# Sheet1.net
KiCad netlist of a schematic drawn in Altium Designer
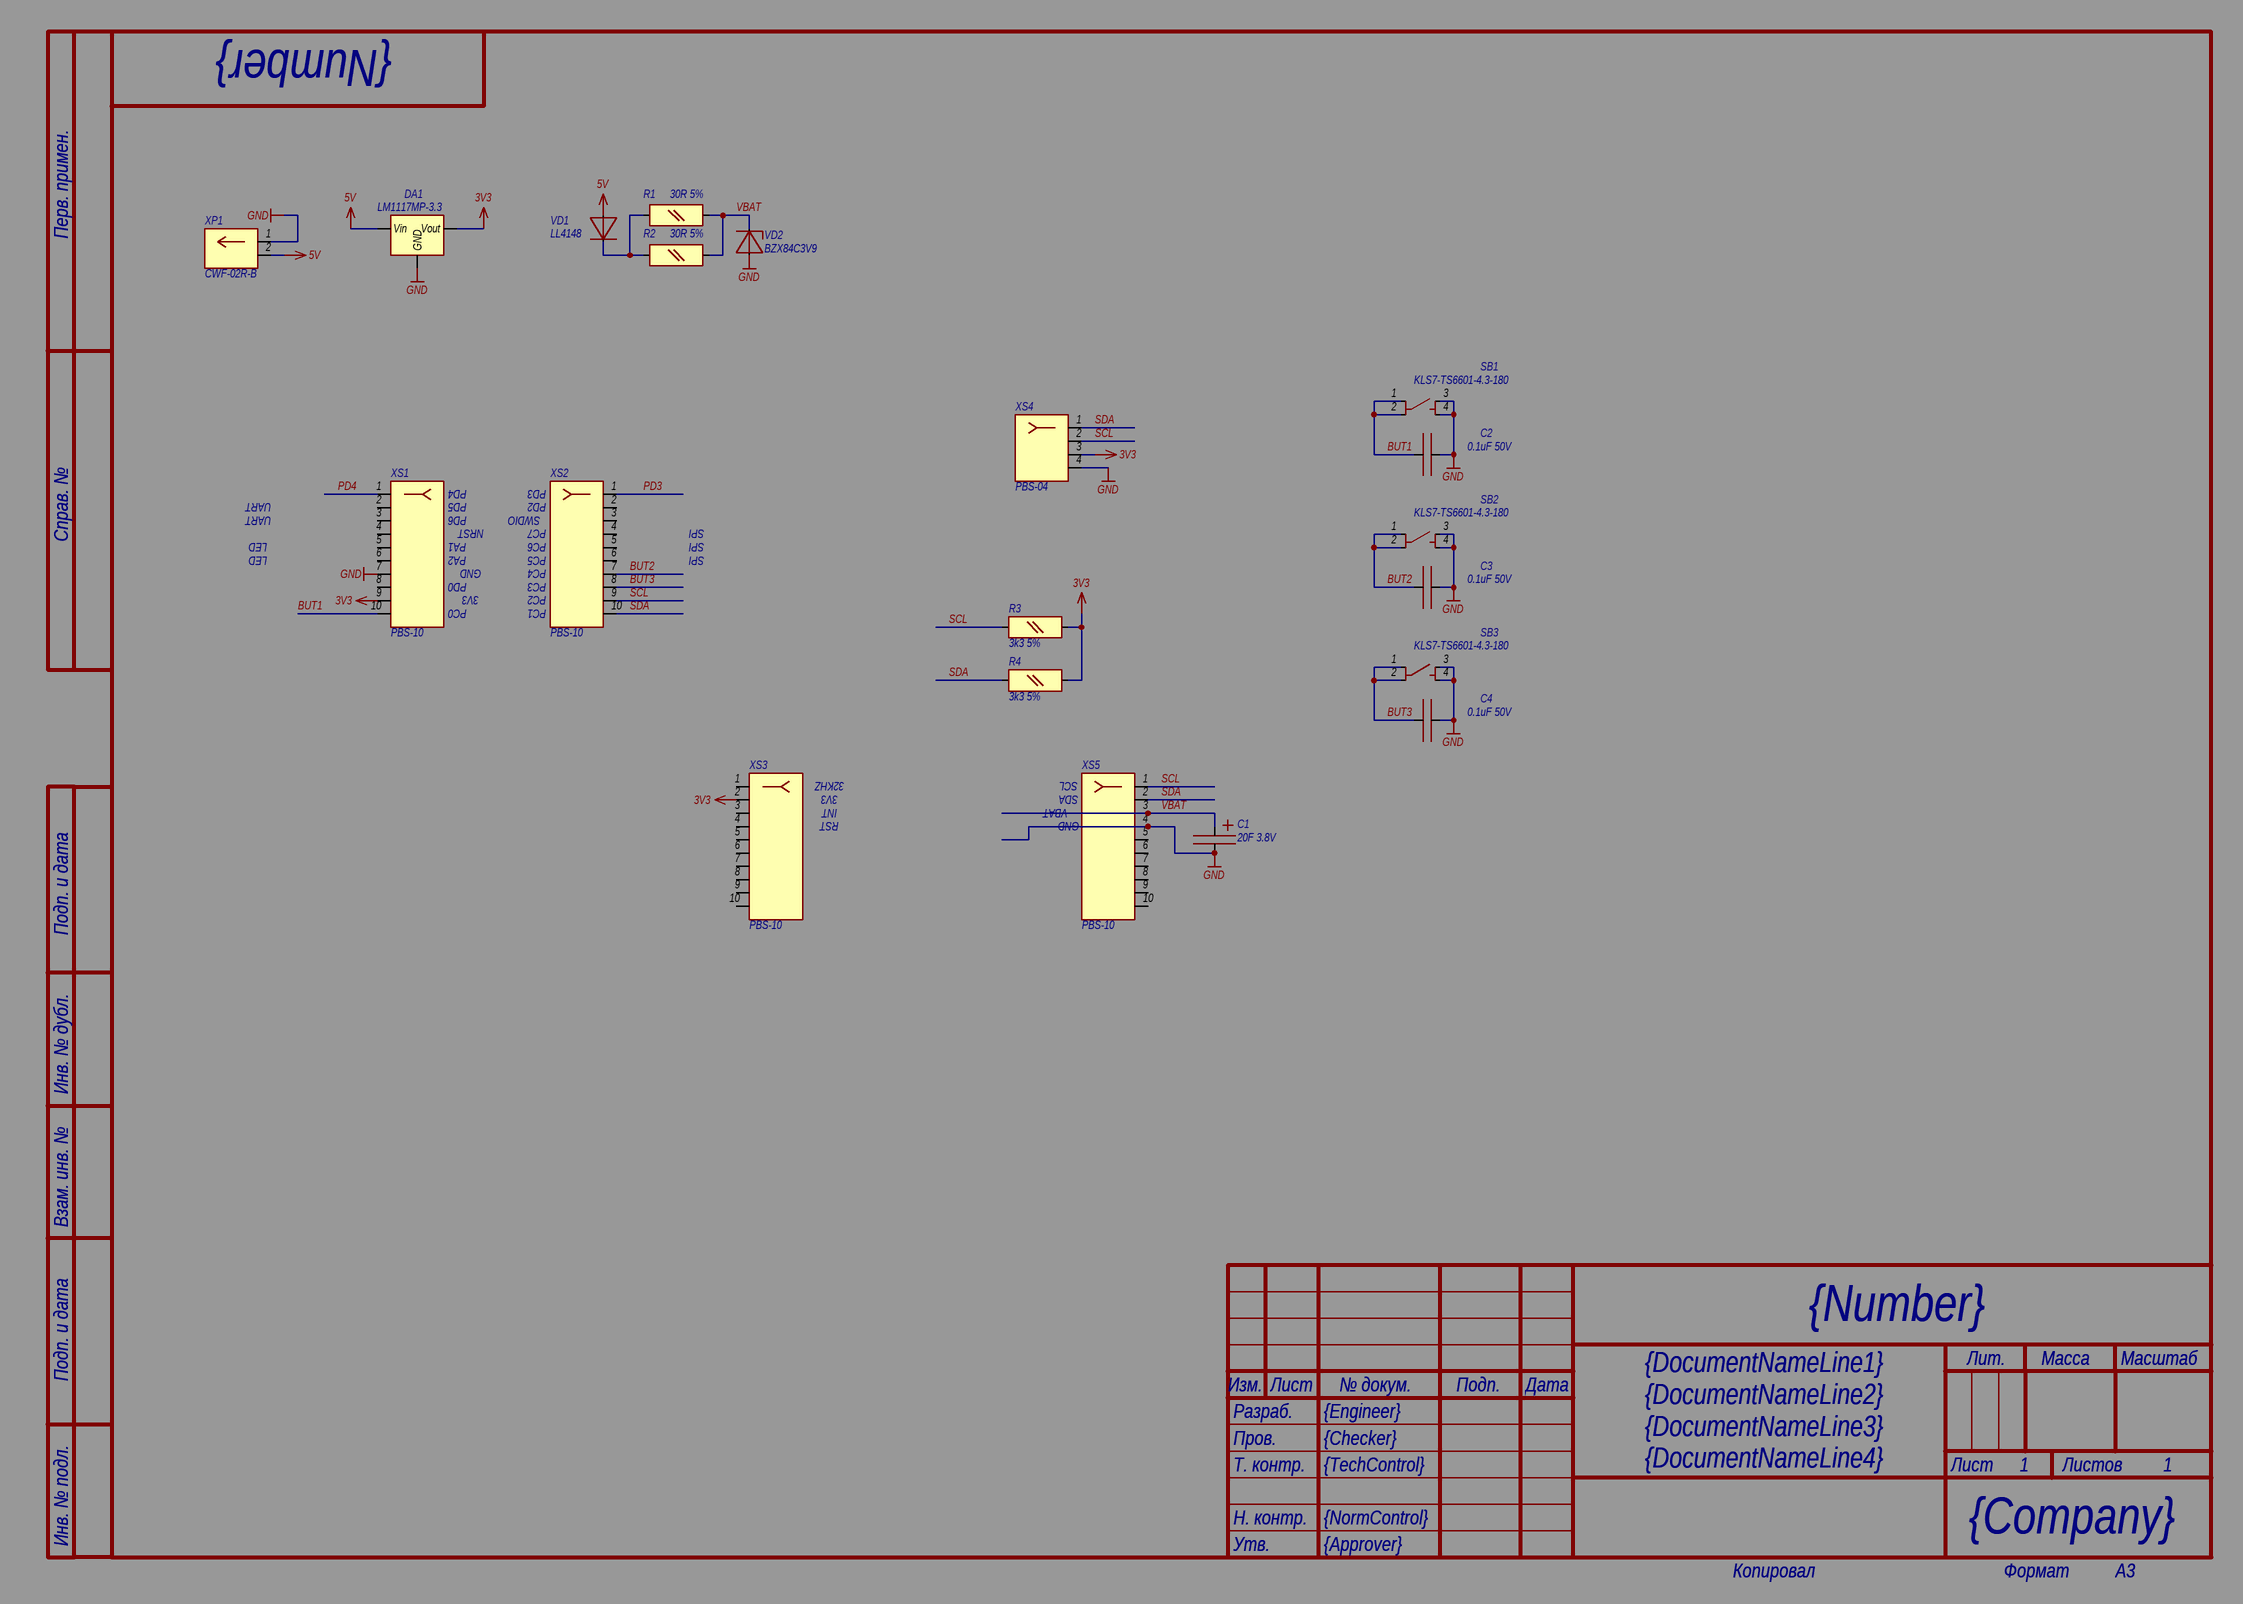
[diagram p0: Sheet1.SchDoc]

(export (version "E")
  (design (tool "Eeschema 10.0.6"))
  (components
    (comp (ref "C1")
      (value "20F 3.8V")
      (footprint "LIC0813")
      (description "Ионистор 20F 3.8V 0813")
      (fields (field (name "PART NUMBER") "LIC 0813 206"))
      (libsource (lib "ATwiceDB") (part "Cap_plus"))
    )
    (comp (ref "C2")
      (value "0.1uF 50V")
      (footprint "CAP SMD0805")
      (description "Конденсатор керамический SMD 0805 0.1uF 50V ±20%")
      (fields (field (name "PART NUMBER") "Cap 0805 0.1uF 50V"))
      (libsource (lib "ATwiceDB") (part "Cap"))
    )
    (comp (ref "C3")
      (value "0.1uF 50V")
      (footprint "CAP SMD0805")
      (description "Конденсатор керамический SMD 0805 0.1uF 50V ±20%")
      (fields (field (name "PART NUMBER") "Cap 0805 0.1uF 50V"))
      (libsource (lib "ATwiceDB") (part "Cap"))
    )
    (comp (ref "C4")
      (value "0.1uF 50V")
      (footprint "CAP SMD0805")
      (description "Конденсатор керамический SMD 0805 0.1uF 50V ±20%")
      (fields (field (name "PART NUMBER") "Cap 0805 0.1uF 50V"))
      (libsource (lib "ATwiceDB") (part "Cap"))
    )
    (comp (ref "DA1")
      (value "LM1117MP-3.3")
      (footprint "SOT223")
      (description "LDO стабилизатор")
      (libsource (lib "ATwiceDB") (part "LM1117"))
    )
    (comp (ref "R1")
      (value "30R 5%")
      (footprint "SMD 0805")
      (description "Резистор SMD 0805 30R 5%")
      (fields (field (name "PART NUMBER") "Res 0805 30R 5%"))
      (libsource (lib "ATwiceDB") (part "Res_0125"))
    )
    (comp (ref "R2")
      (value "30R 5%")
      (footprint "SMD 0805")
      (description "Резистор SMD 0805 30R 5%")
      (fields (field (name "PART NUMBER") "Res 0805 30R 5%"))
      (libsource (lib "ATwiceDB") (part "Res_0125"))
    )
    (comp (ref "R3")
      (value "3k3 5%")
      (footprint "SMD 0805")
      (description "Резистор SMD 0805 3k3 5%")
      (fields (field (name "PART NUMBER") "Res 0805 3k3 5%"))
      (libsource (lib "ATwiceDB") (part "Res_0125"))
    )
    (comp (ref "R4")
      (value "3k3 5%")
      (footprint "SMD 0805")
      (description "Резистор SMD 0805 3k3 5%")
      (fields (field (name "PART NUMBER") "Res 0805 3k3 5%"))
      (libsource (lib "ATwiceDB") (part "Res_0125"))
    )
    (comp (ref "SB1")
      (value "KLS7-TS6601-4.3-180")
      (footprint "KLS7-TS6601-4.3-180")
      (description "Кнопка тактовая KLS7-TS6601 6х6х4,3мм")
      (libsource (lib "ATwiceDB") (part "SB_TACT"))
    )
    (comp (ref "SB2")
      (value "KLS7-TS6601-4.3-180")
      (footprint "KLS7-TS6601-4.3-180")
      (description "Кнопка тактовая KLS7-TS6601 6х6х4,3мм")
      (libsource (lib "ATwiceDB") (part "SB_TACT"))
    )
    (comp (ref "SB3")
      (value "KLS7-TS6601-4.3-180")
      (footprint "KLS7-TS6601-4.3-180")
      (description "Кнопка тактовая KLS7-TS6601 6х6х4,3мм")
      (libsource (lib "ATwiceDB") (part "SB_TACT"))
    )
    (comp (ref "VD1")
      (value "LL4148")
      (footprint "MINIMELF")
      (description "Диод LL4148")
      (libsource (lib "ATwiceDB") (part "Diode"))
    )
    (comp (ref "VD2")
      (value "BZX84C3V9")
      (footprint "SOT23_1A3C")
      (description "Стабилитрон BZX84C3V9 SOT23")
      (libsource (lib "ATwiceDB") (part "Stab"))
    )
    (comp (ref "XP1")
      (value "CWF-02R-B")
      (footprint "CWF-02R-B")
      (description "Разъём CWF-02R-B вилка угловая 2,50мм тип B")
      (libsource (lib "ATwiceDB") (part "Conn_XP02"))
    )
    (comp (ref "XS1")
      (value "PBS-10")
      (footprint "PBS-10")
      (description "Разъём PBS-10 гнездо однорядное 2,54мм")
      (libsource (lib "") (part "Conn_XS10_1"))
    )
    (comp (ref "XS2")
      (value "PBS-10")
      (footprint "PBS-10")
      (description "Разъём PBS-10 гнездо однорядное 2,54мм")
      (libsource (lib "ATwiceDB") (part "Conn_XS10"))
    )
    (comp (ref "XS3")
      (value "PBS-10")
      (footprint "PBS-10")
      (description "Разъём PBS-10 гнездо однорядное 2,54мм")
      (libsource (lib "") (part "Conn_XS10_1"))
    )
    (comp (ref "XS4")
      (value "PBS-04")
      (footprint "PBS-04")
      (description "Разъём PBS-04 гнездо однорядное 2,54мм")
      (libsource (lib "ATwiceDB") (part "Conn_XS04"))
    )
    (comp (ref "XS5")
      (value "PBS-10")
      (footprint "PBS-10")
      (description "Разъём PBS-10 гнездо однорядное 2,54мм")
      (libsource (lib "ATwiceDB") (part "Conn_XS10"))
    )
  )
  (nets
    (net (code "1") (name "/BUT1") (class "Default")
      (node (ref "C2") (pin "1") (pinfunction "1_1") (pintype "passive"))
      (node (ref "SB1") (pin "1") (pinfunction "1_1") (pintype "passive"))
      (node (ref "SB1") (pin "2") (pinfunction "2_2") (pintype "passive"))
      (node (ref "XS1") (pin "10") (pintype "passive"))
    )
    (net (code "2") (name "/BUT2") (class "Default")
      (node (ref "C3") (pin "1") (pinfunction "1_1") (pintype "passive"))
      (node (ref "SB2") (pin "1") (pinfunction "1_1") (pintype "passive"))
      (node (ref "SB2") (pin "2") (pinfunction "2_2") (pintype "passive"))
      (node (ref "XS2") (pin "7") (pintype "passive"))
    )
    (net (code "3") (name "/BUT3") (class "Default")
      (node (ref "C4") (pin "1") (pinfunction "1_1") (pintype "passive"))
      (node (ref "SB3") (pin "1") (pinfunction "1_1") (pintype "passive"))
      (node (ref "SB3") (pin "2") (pinfunction "2_2") (pintype "passive"))
      (node (ref "XS2") (pin "8") (pintype "passive"))
    )
    (net (code "4") (name "/PD3") (class "Default") (node (ref "XS2") (pin "1") (pintype "passive")))
    (net (code "5") (name "/PD4") (class "Default") (node (ref "XS1") (pin "1") (pintype "passive")))
    (net (code "6") (name "/SCL") (class "Default")
      (node (ref "R3") (pin "1") (pinfunction "1_1") (pintype "passive"))
      (node (ref "XS2") (pin "9") (pintype "passive"))
      (node (ref "XS4") (pin "2") (pintype "passive"))
      (node (ref "XS5") (pin "1") (pintype "passive"))
    )
    (net (code "7") (name "/SDA") (class "Default")
      (node (ref "R4") (pin "1") (pinfunction "1_1") (pintype "passive"))
      (node (ref "XS2") (pin "10") (pintype "passive"))
      (node (ref "XS4") (pin "1") (pintype "passive"))
      (node (ref "XS5") (pin "2") (pintype "passive"))
    )
    (net (code "8") (name "/VBAT") (class "Default")
      (node (ref "C1") (pin "1") (pinfunction "1_1") (pintype "passive"))
      (node (ref "R1") (pin "2") (pinfunction "2_2") (pintype "passive"))
      (node (ref "R2") (pin "2") (pinfunction "2_2") (pintype "passive"))
      (node (ref "VD2") (pin "C") (pinfunction "C_C") (pintype "passive"))
      (node (ref "XS5") (pin "3") (pintype "passive"))
    )
    (net (code "9") (name "3V3") (class "Default")
      (node (ref "DA1") (pin "2") (pinfunction "Vout_2") (pintype "passive"))
      (node (ref "R3") (pin "2") (pinfunction "2_2") (pintype "passive"))
      (node (ref "R4") (pin "2") (pinfunction "2_2") (pintype "passive"))
      (node (ref "XS1") (pin "9") (pintype "passive"))
      (node (ref "XS3") (pin "2") (pintype "passive"))
      (node (ref "XS4") (pin "3") (pintype "passive"))
    )
    (net (code "10") (name "5V") (class "Default")
      (node (ref "DA1") (pin "3") (pinfunction "Vin_3") (pintype "passive"))
      (node (ref "VD1") (pin "A") (pinfunction "A_A") (pintype "passive"))
      (node (ref "XP1") (pin "2") (pintype "passive"))
    )
    (net (code "11") (name "GND") (class "Default")
      (node (ref "C1") (pin "2") (pinfunction "2_2") (pintype "passive"))
      (node (ref "C2") (pin "2") (pinfunction "2_2") (pintype "passive"))
      (node (ref "C3") (pin "2") (pinfunction "2_2") (pintype "passive"))
      (node (ref "C4") (pin "2") (pinfunction "2_2") (pintype "passive"))
      (node (ref "DA1") (pin "1") (pinfunction "GND_1") (pintype "passive"))
      (node (ref "SB1") (pin "3") (pinfunction "3_3") (pintype "passive"))
      (node (ref "SB1") (pin "4") (pintype "passive"))
      (node (ref "SB2") (pin "3") (pinfunction "3_3") (pintype "passive"))
      (node (ref "SB2") (pin "4") (pintype "passive"))
      (node (ref "SB3") (pin "3") (pinfunction "3_3") (pintype "passive"))
      (node (ref "SB3") (pin "4") (pintype "passive"))
      (node (ref "VD2") (pin "A") (pinfunction "A_A") (pintype "passive"))
      (node (ref "XP1") (pin "1") (pintype "passive"))
      (node (ref "XS1") (pin "7") (pintype "passive"))
      (node (ref "XS4") (pin "4") (pintype "passive"))
      (node (ref "XS5") (pin "4") (pintype "passive"))
    )
    (net (code "12") (name "Net-(R1-Pad1)") (class "Default")
      (node (ref "R1") (pin "1") (pinfunction "1_1") (pintype "passive"))
      (node (ref "R2") (pin "1") (pinfunction "1_1") (pintype "passive"))
      (node (ref "VD1") (pin "C") (pinfunction "C_C") (pintype "passive"))
    )
    (net (code "13") (name "unconnected-(XS1-Pad2)") (class "Default")
      (node (ref "XS1") (pin "2") (pintype "passive"))
    )
    (net (code "14") (name "unconnected-(XS1-Pad3)") (class "Default")
      (node (ref "XS1") (pin "3") (pintype "passive"))
    )
    (net (code "15") (name "unconnected-(XS1-Pad4)") (class "Default")
      (node (ref "XS1") (pin "4") (pintype "passive"))
    )
    (net (code "16") (name "unconnected-(XS1-Pad5)") (class "Default")
      (node (ref "XS1") (pin "5") (pintype "passive"))
    )
    (net (code "17") (name "unconnected-(XS1-Pad6)") (class "Default")
      (node (ref "XS1") (pin "6") (pintype "passive"))
    )
    (net (code "18") (name "unconnected-(XS1-Pad8)") (class "Default")
      (node (ref "XS1") (pin "8") (pintype "passive"))
    )
    (net (code "19") (name "unconnected-(XS2-Pad2)") (class "Default")
      (node (ref "XS2") (pin "2") (pintype "passive"))
    )
    (net (code "20") (name "unconnected-(XS2-Pad3)") (class "Default")
      (node (ref "XS2") (pin "3") (pintype "passive"))
    )
    (net (code "21") (name "unconnected-(XS2-Pad4)") (class "Default")
      (node (ref "XS2") (pin "4") (pintype "passive"))
    )
    (net (code "22") (name "unconnected-(XS2-Pad5)") (class "Default")
      (node (ref "XS2") (pin "5") (pintype "passive"))
    )
    (net (code "23") (name "unconnected-(XS2-Pad6)") (class "Default")
      (node (ref "XS2") (pin "6") (pintype "passive"))
    )
    (net (code "24") (name "unconnected-(XS3-Pad1)") (class "Default")
      (node (ref "XS3") (pin "1") (pintype "passive"))
    )
    (net (code "25") (name "unconnected-(XS3-Pad3)") (class "Default")
      (node (ref "XS3") (pin "3") (pintype "passive"))
    )
    (net (code "26") (name "unconnected-(XS3-Pad4)") (class "Default")
      (node (ref "XS3") (pin "4") (pintype "passive"))
    )
    (net (code "27") (name "unconnected-(XS3-Pad5)") (class "Default")
      (node (ref "XS3") (pin "5") (pintype "passive"))
    )
    (net (code "28") (name "unconnected-(XS3-Pad6)") (class "Default")
      (node (ref "XS3") (pin "6") (pintype "passive"))
    )
    (net (code "29") (name "unconnected-(XS3-Pad7)") (class "Default")
      (node (ref "XS3") (pin "7") (pintype "passive"))
    )
    (net (code "30") (name "unconnected-(XS3-Pad8)") (class "Default")
      (node (ref "XS3") (pin "8") (pintype "passive"))
    )
    (net (code "31") (name "unconnected-(XS3-Pad9)") (class "Default")
      (node (ref "XS3") (pin "9") (pintype "passive"))
    )
    (net (code "32") (name "unconnected-(XS3-Pad10)") (class "Default")
      (node (ref "XS3") (pin "10") (pintype "passive"))
    )
    (net (code "33") (name "unconnected-(XS5-Pad5)") (class "Default")
      (node (ref "XS5") (pin "5") (pintype "passive"))
    )
    (net (code "34") (name "unconnected-(XS5-Pad6)") (class "Default")
      (node (ref "XS5") (pin "6") (pintype "passive"))
    )
    (net (code "35") (name "unconnected-(XS5-Pad7)") (class "Default")
      (node (ref "XS5") (pin "7") (pintype "passive"))
    )
    (net (code "36") (name "unconnected-(XS5-Pad8)") (class "Default")
      (node (ref "XS5") (pin "8") (pintype "passive"))
    )
    (net (code "37") (name "unconnected-(XS5-Pad9)") (class "Default")
      (node (ref "XS5") (pin "9") (pintype "passive"))
    )
    (net (code "38") (name "unconnected-(XS5-Pad10)") (class "Default")
      (node (ref "XS5") (pin "10") (pintype "passive"))
    )
  )
)
